# MainBoard.net
KiCad netlist of a schematic drawn in EAGLE
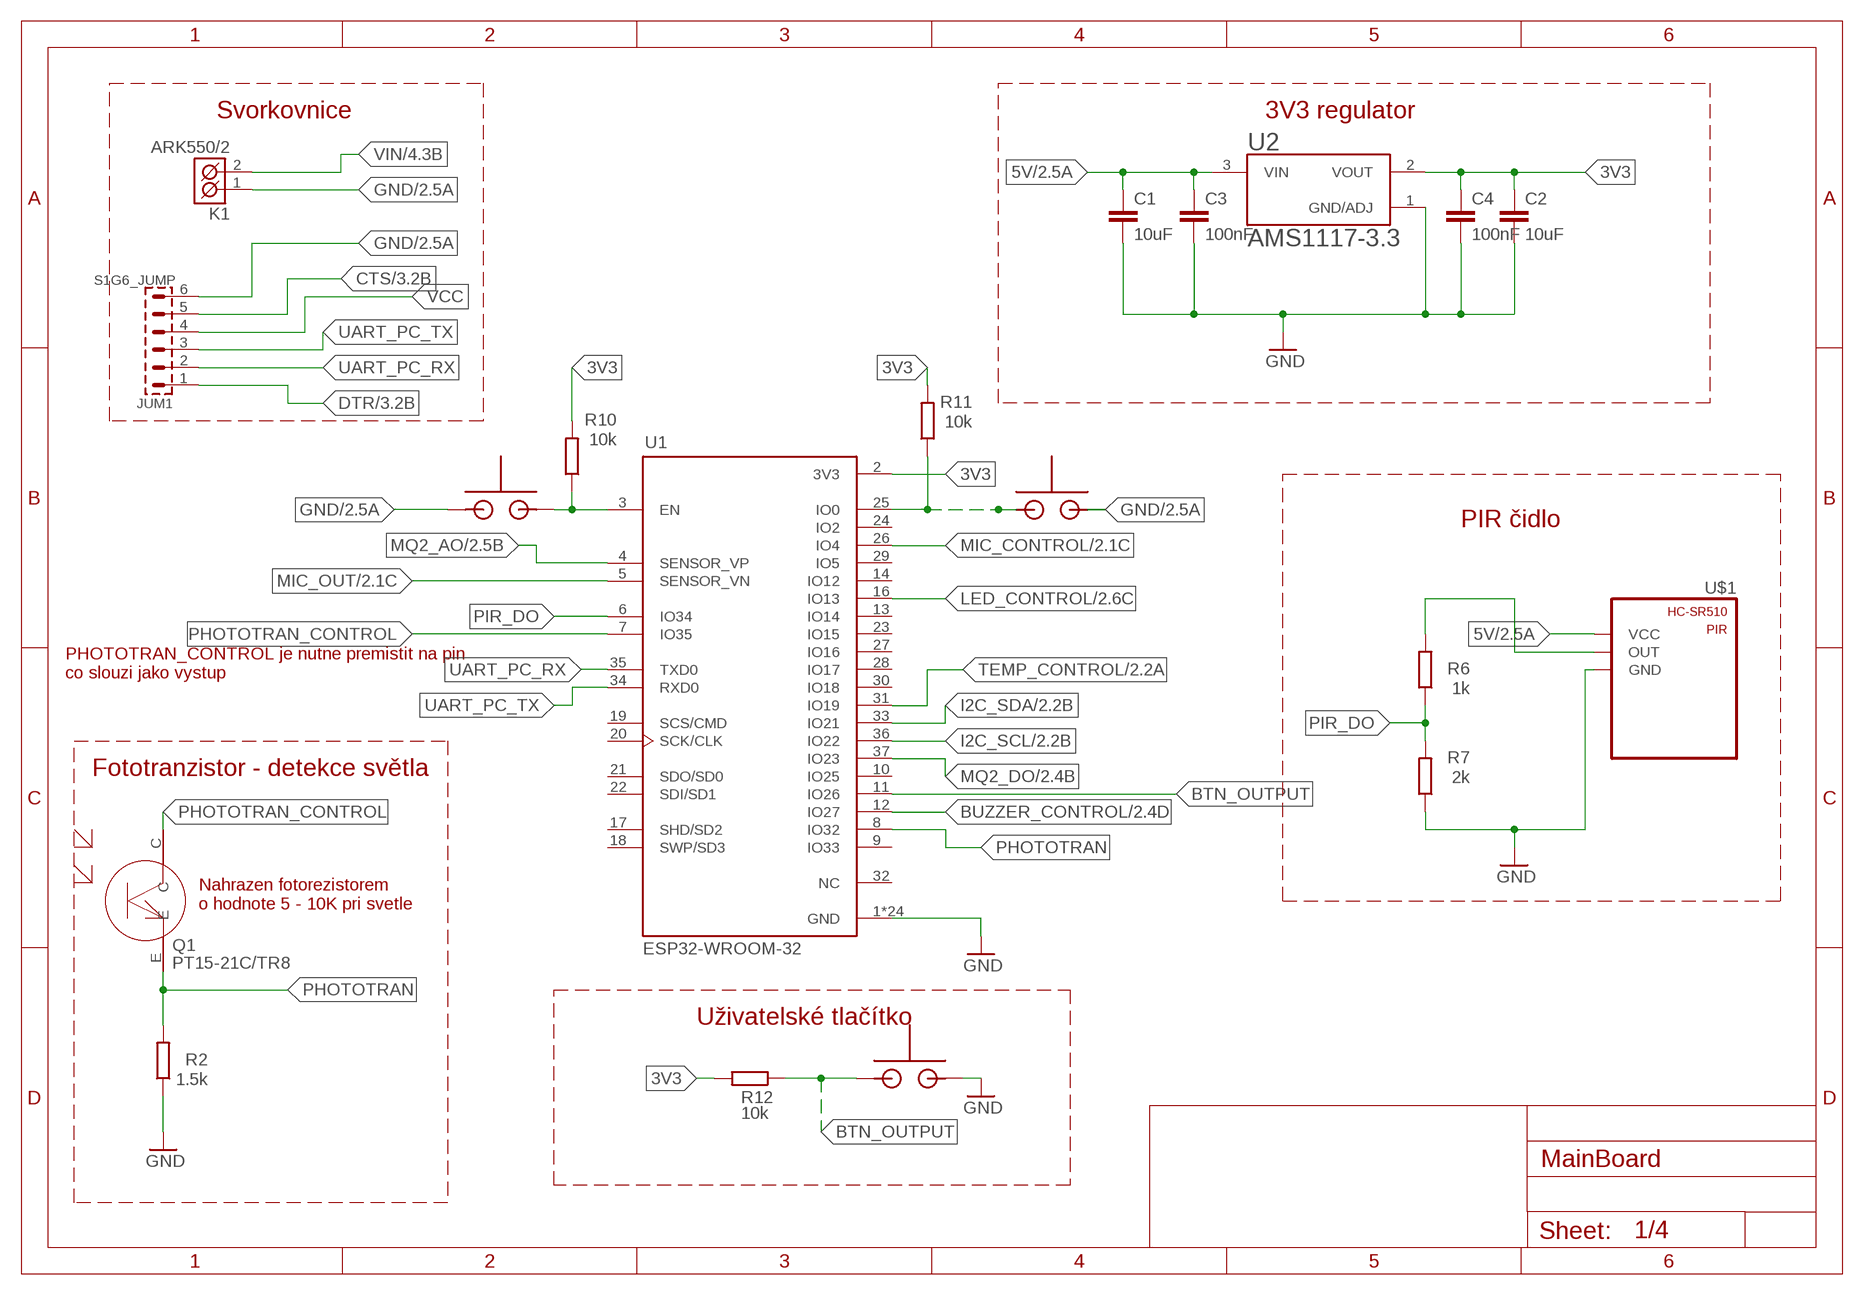
[diagram p0: schematic, sheet 1]
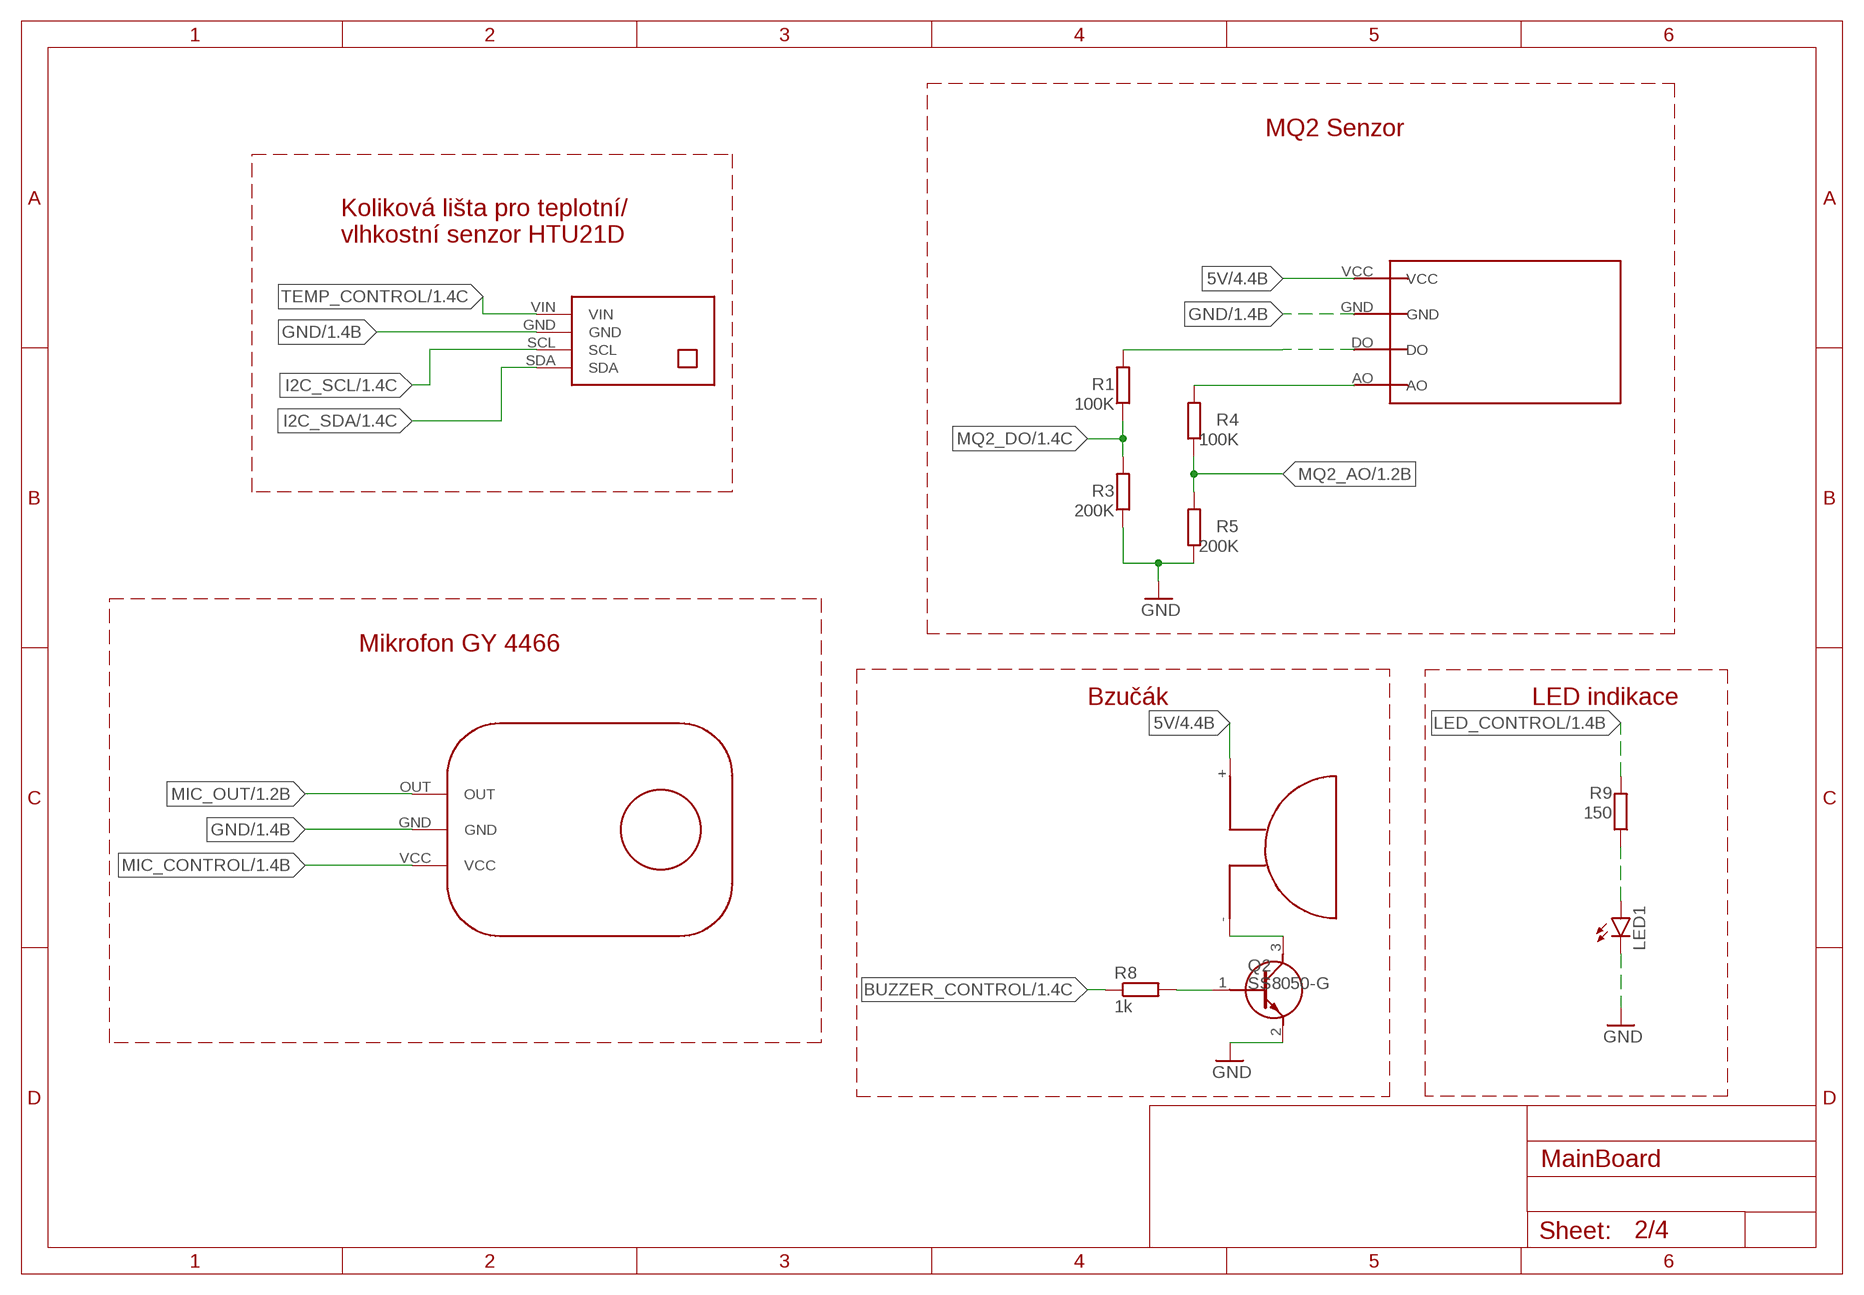
[diagram p1: schematic, sheet 2]
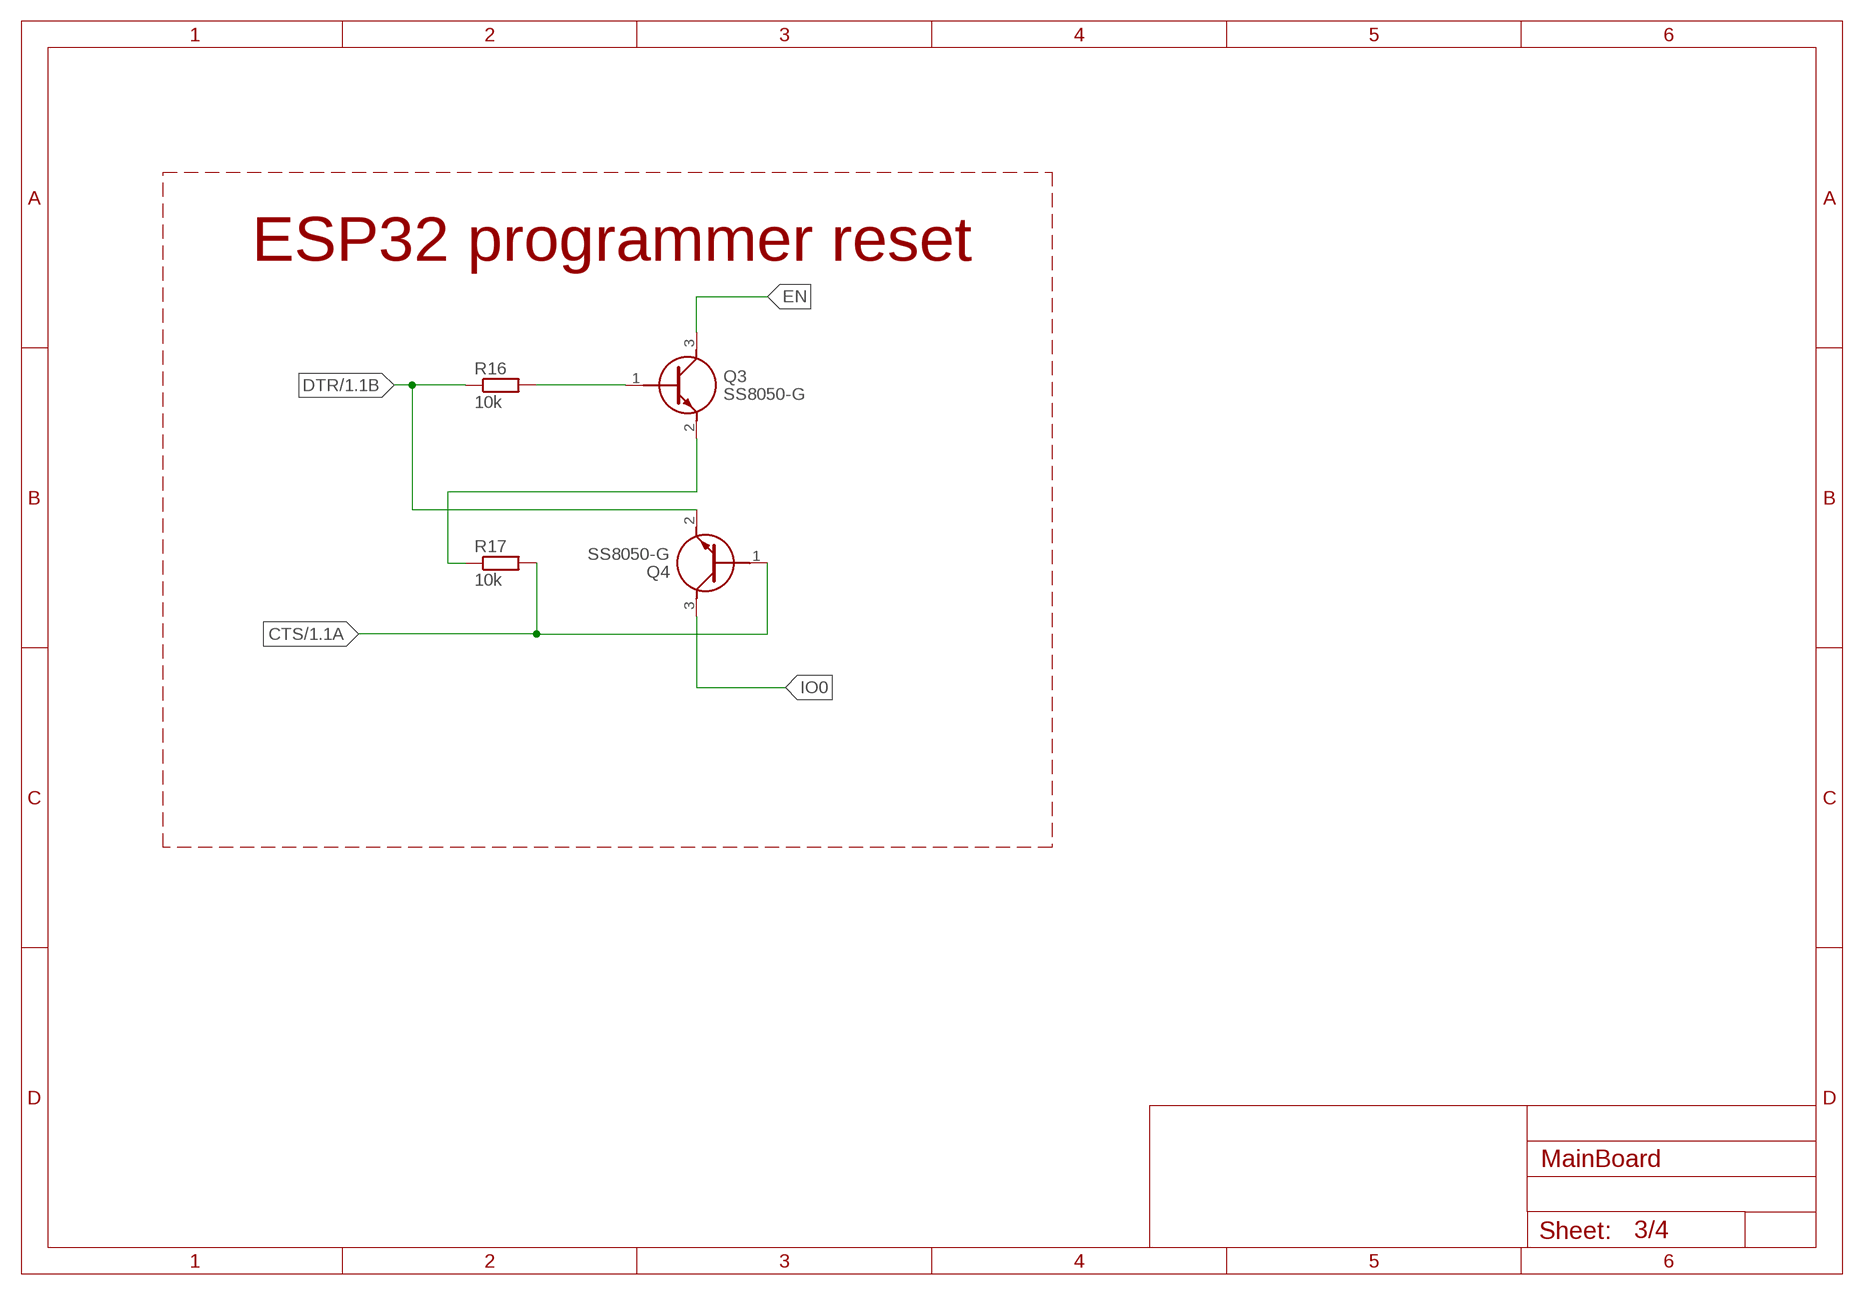
[diagram p2: schematic, sheet 3]
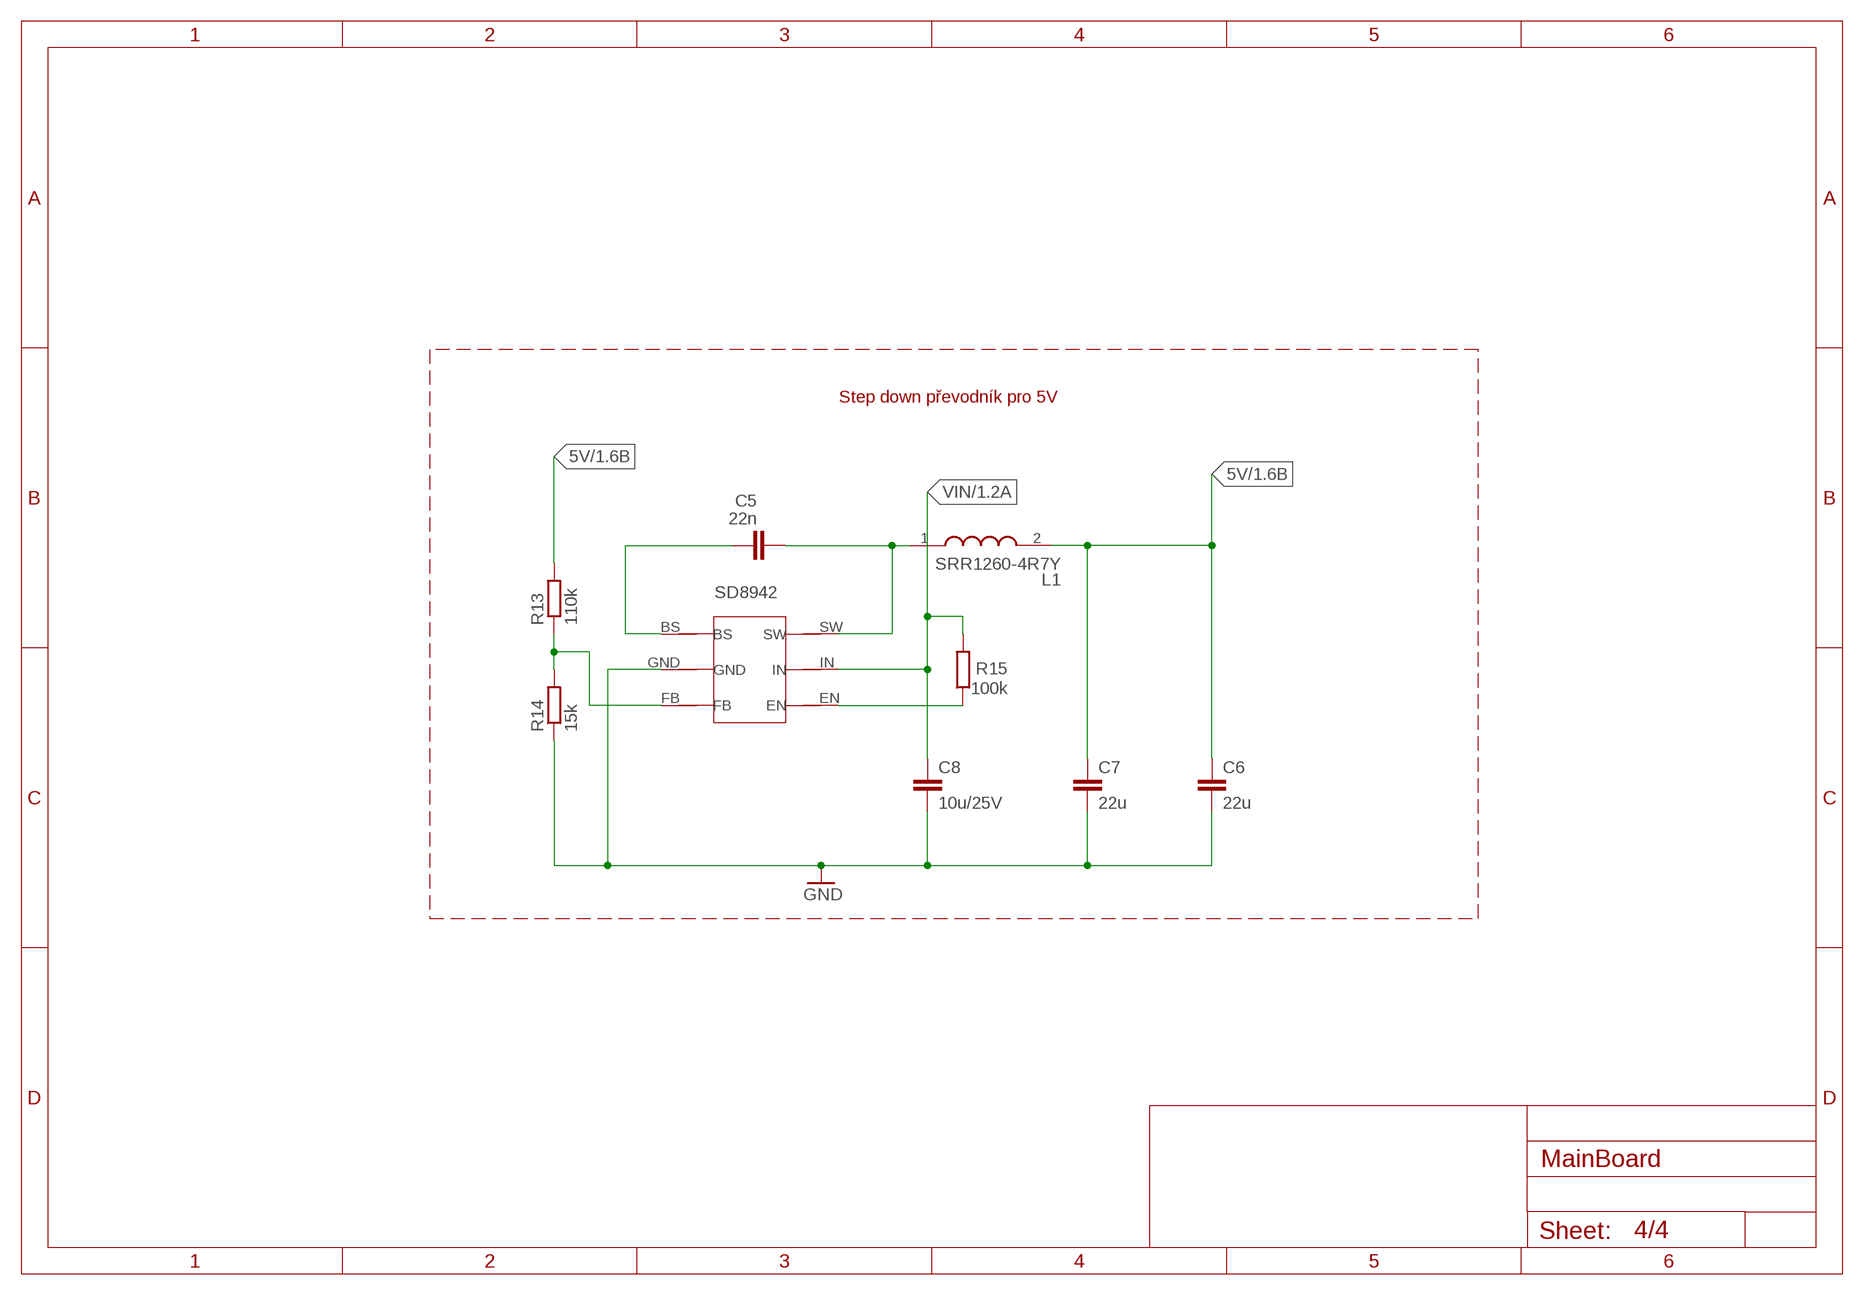
[diagram p3: schematic, sheet 4]

(export (version "E")
  (design (tool "Eeschema 10.0.6"))
  (components
    (comp (ref "C1")
      (value "10uF")
      (footprint "eagle-import:C0805")
      (libsource (lib "eagle-import") (part "C-EUC0805"))
    )
    (comp (ref "C2")
      (value "10uF")
      (footprint "eagle-import:C0805")
      (libsource (lib "eagle-import") (part "C-EUC0805"))
    )
    (comp (ref "C3")
      (value "100nF")
      (footprint "eagle-import:C0805")
      (libsource (lib "eagle-import") (part "C-EUC0805"))
    )
    (comp (ref "C4")
      (value "100nF")
      (footprint "eagle-import:C0805")
      (libsource (lib "eagle-import") (part "C-EUC0805"))
    )
    (comp (ref "JUM1")
      (value "S1G6_JUMP")
      (footprint "eagle-import:S1G6_JUM")
      (libsource (lib "eagle-import") (part "S1G6_JUMP"))
    )
    (comp (ref "K1")
      (value "ARK550/2")
      (footprint "eagle-import:ARK550_2")
      (libsource (lib "eagle-import") (part "ARK550/2"))
    )
    (comp (ref "Q1")
      (value "PT15-21C/TR8")
      (footprint "eagle-import:PT15-21C_TR8")
      (libsource (lib "eagle-import") (part "PT15-21C/TR8"))
    )
    (comp (ref "R2")
      (value "1.5k")
      (footprint "eagle-import:R0805")
      (libsource (lib "eagle-import") (part "R-EU_R0805"))
    )
    (comp (ref "R6")
      (value "1k")
      (footprint "eagle-import:R0805")
      (libsource (lib "eagle-import") (part "R-EU_R0805"))
    )
    (comp (ref "R7")
      (value "2k")
      (footprint "eagle-import:R0805")
      (libsource (lib "eagle-import") (part "R-EU_R0805"))
    )
    (comp (ref "R10")
      (value "10k")
      (footprint "eagle-import:R0805")
      (libsource (lib "eagle-import") (part "R-EU_R0805"))
    )
    (comp (ref "R11")
      (value "10k")
      (footprint "eagle-import:R0805")
      (libsource (lib "eagle-import") (part "R-EU_R0805"))
    )
    (comp (ref "R12")
      (value "10k")
      (footprint "eagle-import:R0805")
      (libsource (lib "eagle-import") (part "R-EU_R0805"))
    )
    (comp (ref "U$1")
      (value "HC-SR501")
      (footprint "eagle-import:HC-SR501")
      (libsource (lib "eagle-import") (part "HC-SR501"))
    )
    (comp (ref "U$6")
      (value "TS6604B")
      (footprint "eagle-import:TS6604B")
      (libsource (lib "eagle-import") (part "TS6604B"))
    )
    (comp (ref "U$7")
      (value "TS6604B")
      (footprint "eagle-import:TS6604B")
      (libsource (lib "eagle-import") (part "TS6604B"))
    )
    (comp (ref "U$8")
      (value "TS6604B")
      (footprint "eagle-import:TS6604B")
      (libsource (lib "eagle-import") (part "TS6604B"))
    )
    (comp (ref "U1")
      (value "ESP32-WROOM-32")
      (footprint "eagle-import:MODULE_ESP32-WROOM-32")
      (fields (field (name "MF") "Espressif Systems"))
      (libsource (lib "eagle-import") (part "ESP32-WROOM-32"))
    )
    (comp (ref "U2")
      (value "AMS1117-3.3")
      (footprint "eagle-import:SOT229P700X180-4N")
      (fields (field (name "MF") "Advanced Monolithic Systems"))
      (libsource (lib "eagle-import") (part "AMS1117-3.3"))
    )
    (comp (ref "LED1")
      (value "LEDCHIP-LED0805")
      (footprint "eagle-import:CHIP-LED0805")
      (libsource (lib "eagle-import") (part "LEDCHIP-LED0805"))
    )
    (comp (ref "Q2")
      (value "SS8050-G")
      (footprint "eagle-import:SOT95P240X115-3N")
      (fields (field (name "MOUSER_PART_NUMBER") "750-SS8050-G"))
      (libsource (lib "eagle-import") (part "SS8050-G"))
    )
    (comp (ref "R1")
      (value "100K")
      (footprint "eagle-import:R0805")
      (libsource (lib "eagle-import") (part "R-EU_R0805"))
    )
    (comp (ref "R3")
      (value "200K")
      (footprint "eagle-import:R0805")
      (libsource (lib "eagle-import") (part "R-EU_R0805"))
    )
    (comp (ref "R4")
      (value "100K")
      (footprint "eagle-import:R0805")
      (libsource (lib "eagle-import") (part "R-EU_R0805"))
    )
    (comp (ref "R5")
      (value "200K")
      (footprint "eagle-import:R0805")
      (libsource (lib "eagle-import") (part "R-EU_R0805"))
    )
    (comp (ref "R8")
      (value "1k")
      (footprint "eagle-import:R0805")
      (libsource (lib "eagle-import") (part "R-EU_R0805"))
    )
    (comp (ref "R9")
      (value "150")
      (footprint "eagle-import:R0805")
      (libsource (lib "eagle-import") (part "R-EU_R0805"))
    )
    (comp (ref "U$2")
      (value "MQ2")
      (footprint "eagle-import:MQ2")
      (libsource (lib "eagle-import") (part "MQ2"))
    )
    (comp (ref "U$3")
      (value "GY4466")
      (footprint "eagle-import:GY4466")
      (libsource (lib "eagle-import") (part "GY4466"))
    )
    (comp (ref "U$4")
      (value "BUZZER")
      (footprint "eagle-import:BUZZER")
      (libsource (lib "eagle-import") (part "BUZZER"))
    )
    (comp (ref "U$5")
      (value "HTU21D")
      (footprint "eagle-import:HTU21D")
      (libsource (lib "eagle-import") (part "HTU21D"))
    )
    (comp (ref "C5")
      (value "22n")
      (footprint "eagle-import:C0805")
      (libsource (lib "eagle-import") (part "C-EUC0805"))
    )
    (comp (ref "C6")
      (value "22u")
      (footprint "eagle-import:C0805")
      (libsource (lib "eagle-import") (part "C-EUC0805"))
    )
    (comp (ref "C7")
      (value "22u")
      (footprint "eagle-import:C0805")
      (libsource (lib "eagle-import") (part "C-EUC0805"))
    )
    (comp (ref "C8")
      (value "10u/25V")
      (footprint "eagle-import:C0805")
      (libsource (lib "eagle-import") (part "C-EUC0805"))
    )
    (comp (ref "L1")
      (value "SRR1260-4R7Y")
      (footprint "eagle-import:SRR12604R7Y")
      (fields (field (name "MOUSER_PART_NUMBER") "652-SRR1260-4R7Y"))
      (libsource (lib "eagle-import") (part "SRR1260-4R7Y"))
    )
    (comp (ref "R13")
      (value "110k")
      (footprint "eagle-import:R0805")
      (libsource (lib "eagle-import") (part "R-EU_R0805"))
    )
    (comp (ref "R14")
      (value "15k")
      (footprint "eagle-import:R0805")
      (libsource (lib "eagle-import") (part "R-EU_R0805"))
    )
    (comp (ref "R15")
      (value "100k")
      (footprint "eagle-import:R0805")
      (libsource (lib "eagle-import") (part "R-EU_R0805"))
    )
    (comp (ref "U$9")
      (value "SD8942")
      (footprint "eagle-import:SD8942")
      (libsource (lib "eagle-import") (part "SD8942"))
    )
    (comp (ref "Q3")
      (value "SS8050-G")
      (footprint "eagle-import:SOT95P240X115-3N")
      (fields (field (name "MOUSER_PART_NUMBER") "750-SS8050-G"))
      (libsource (lib "eagle-import") (part "SS8050-G"))
    )
    (comp (ref "Q4")
      (value "SS8050-G")
      (footprint "eagle-import:SOT95P240X115-3N")
      (fields (field (name "MOUSER_PART_NUMBER") "750-SS8050-G"))
      (libsource (lib "eagle-import") (part "SS8050-G"))
    )
    (comp (ref "R16")
      (value "10k")
      (footprint "eagle-import:R0805")
      (libsource (lib "eagle-import") (part "R-EU_R0805"))
    )
    (comp (ref "R17")
      (value "10k")
      (footprint "eagle-import:R0805")
      (libsource (lib "eagle-import") (part "R-EU_R0805"))
    )
  )
  (nets
    (net (code "1") (name "3V3") (class "Default")
      (node (ref "C2") (pin "1") (pinfunction "1_1") (pintype "passive"))
      (node (ref "C4") (pin "1") (pinfunction "1_1") (pintype "passive"))
      (node (ref "R10") (pin "2") (pinfunction "2_2") (pintype "passive"))
      (node (ref "R11") (pin "2") (pinfunction "2_2") (pintype "passive"))
      (node (ref "R12") (pin "2") (pinfunction "2_2") (pintype "passive"))
      (node (ref "U1") (pin "2") (pinfunction "3V3_2") (pintype "power_in"))
      (node (ref "U2") (pin "2") (pinfunction "VOUT_2") (pintype "output"))
    )
    (net (code "2") (name "5V") (class "Default")
      (node (ref "C1") (pin "1") (pinfunction "1_1") (pintype "passive"))
      (node (ref "C3") (pin "1") (pinfunction "1_1") (pintype "passive"))
      (node (ref "C6") (pin "1") (pinfunction "1_1") (pintype "passive"))
      (node (ref "C7") (pin "1") (pinfunction "1_1") (pintype "passive"))
      (node (ref "L1") (pin "2") (pinfunction "2_2") (pintype "bidirectional"))
      (node (ref "R13") (pin "2") (pinfunction "2_2") (pintype "passive"))
      (node (ref "U$1") (pin "VCC") (pinfunction "VCC_VCC") (pintype "power_in"))
      (node (ref "U$2") (pin "VCC") (pinfunction "VCC_VCC") (pintype "bidirectional"))
      (node (ref "U$4") (pin "+") (pinfunction "+_+") (pintype "bidirectional"))
      (node (ref "U2") (pin "3") (pinfunction "VIN_3") (pintype "input"))
    )
    (net (code "3") (name "BTN_OUTPUT") (class "Default")
      (node (ref "R12") (pin "1") (pinfunction "1_1") (pintype "passive"))
      (node (ref "U$8") (pin "+") (pinfunction "+_+") (pintype "bidirectional"))
      (node (ref "U1") (pin "11") (pinfunction "IO26_11") (pintype "bidirectional"))
    )
    (net (code "4") (name "BUZZER_CONTROL") (class "Default")
      (node (ref "R8") (pin "1") (pinfunction "1_1") (pintype "passive"))
      (node (ref "U1") (pin "12") (pinfunction "IO27_12") (pintype "bidirectional"))
    )
    (net (code "5") (name "CTS") (class "Default")
      (node (ref "JUM1") (pin "5") (pinfunction "5_5") (pintype "passive"))
      (node (ref "Q4") (pin "1") (pinfunction "B_1") (pintype "bidirectional"))
      (node (ref "R17") (pin "2") (pinfunction "2_2") (pintype "passive"))
    )
    (net (code "6") (name "DTR") (class "Default")
      (node (ref "JUM1") (pin "1") (pinfunction "1_1") (pintype "passive"))
      (node (ref "Q4") (pin "2") (pinfunction "E_2") (pintype "bidirectional"))
      (node (ref "R16") (pin "1") (pinfunction "1_1") (pintype "passive"))
    )
    (net (code "7") (name "EN") (class "Default")
      (node (ref "Q3") (pin "3") (pinfunction "C_3") (pintype "bidirectional"))
      (node (ref "R10") (pin "1") (pinfunction "1_1") (pintype "passive"))
      (node (ref "U$6") (pin "+") (pinfunction "+_+") (pintype "bidirectional"))
      (node (ref "U1") (pin "3") (pinfunction "EN_3") (pintype "input"))
    )
    (net (code "8") (name "GND") (class "Default")
      (node (ref "C1") (pin "2") (pinfunction "2_2") (pintype "passive"))
      (node (ref "C2") (pin "2") (pinfunction "2_2") (pintype "passive"))
      (node (ref "C3") (pin "2") (pinfunction "2_2") (pintype "passive"))
      (node (ref "C4") (pin "2") (pinfunction "2_2") (pintype "passive"))
      (node (ref "C6") (pin "2") (pinfunction "2_2") (pintype "passive"))
      (node (ref "C7") (pin "2") (pinfunction "2_2") (pintype "passive"))
      (node (ref "C8") (pin "2") (pinfunction "2_2") (pintype "passive"))
      (node (ref "JUM1") (pin "6") (pinfunction "6_6") (pintype "passive"))
      (node (ref "K1") (pin "1") (pinfunction "K1_1") (pintype "passive"))
      (node (ref "LED1") (pin "C") (pinfunction "C_C") (pintype "passive"))
      (node (ref "Q2") (pin "2") (pinfunction "E_2") (pintype "bidirectional"))
      (node (ref "R14") (pin "1") (pinfunction "1_1") (pintype "passive"))
      (node (ref "R2") (pin "1") (pinfunction "1_1") (pintype "passive"))
      (node (ref "R3") (pin "1") (pinfunction "1_1") (pintype "passive"))
      (node (ref "R5") (pin "1") (pinfunction "1_1") (pintype "passive"))
      (node (ref "R7") (pin "1") (pinfunction "1_1") (pintype "passive"))
      (node (ref "U$1") (pin "GND") (pinfunction "GND_GND") (pintype "power_in"))
      (node (ref "U$2") (pin "GND") (pinfunction "GND_GND") (pintype "bidirectional"))
      (node (ref "U$3") (pin "GND") (pinfunction "GND_GND") (pintype "bidirectional"))
      (node (ref "U$5") (pin "GND") (pinfunction "GND_GND") (pintype "bidirectional"))
      (node (ref "U$6") (pin "-") (pinfunction "-_-") (pintype "bidirectional"))
      (node (ref "U$7") (pin "-") (pinfunction "-_-") (pintype "bidirectional"))
      (node (ref "U$8") (pin "-") (pinfunction "-_-") (pintype "bidirectional"))
      (node (ref "U$9") (pin "GND") (pinfunction "GND_GND") (pintype "bidirectional"))
      (node (ref "U1") (pin "1") (pinfunction "GND_1") (pintype "power_in"))
      (node (ref "U1") (pin "15") (pinfunction "GND_15") (pintype "power_in"))
      (node (ref "U1") (pin "38") (pinfunction "GND_38") (pintype "power_in"))
      (node (ref "U1") (pin "39_1") (pinfunction "GND_39_1") (pintype "power_in"))
      (node (ref "U1") (pin "39_10") (pinfunction "GND_39_10") (pintype "power_in"))
      (node (ref "U1") (pin "39_11") (pinfunction "GND_39_11") (pintype "power_in"))
      (node (ref "U1") (pin "39_12") (pinfunction "GND_39_12") (pintype "power_in"))
      (node (ref "U1") (pin "39_13") (pinfunction "GND_39_13") (pintype "power_in"))
      (node (ref "U1") (pin "39_14") (pinfunction "GND_39_14") (pintype "power_in"))
      (node (ref "U1") (pin "39_15") (pinfunction "GND_39_15") (pintype "power_in"))
      (node (ref "U1") (pin "39_16") (pinfunction "GND_39_16") (pintype "power_in"))
      (node (ref "U1") (pin "39_17") (pinfunction "GND_39_17") (pintype "power_in"))
      (node (ref "U1") (pin "39_18") (pinfunction "GND_39_18") (pintype "power_in"))
      (node (ref "U1") (pin "39_19") (pinfunction "GND_39_19") (pintype "power_in"))
      (node (ref "U1") (pin "39_2") (pinfunction "GND_39_2") (pintype "power_in"))
      (node (ref "U1") (pin "39_20") (pinfunction "GND_39_20") (pintype "power_in"))
      (node (ref "U1") (pin "39_21") (pinfunction "GND_39_21") (pintype "power_in"))
      (node (ref "U1") (pin "39_3") (pinfunction "GND_39_3") (pintype "power_in"))
      (node (ref "U1") (pin "39_4") (pinfunction "GND_39_4") (pintype "power_in"))
      (node (ref "U1") (pin "39_5") (pinfunction "GND_39_5") (pintype "power_in"))
      (node (ref "U1") (pin "39_6") (pinfunction "GND_39_6") (pintype "power_in"))
      (node (ref "U1") (pin "39_7") (pinfunction "GND_39_7") (pintype "power_in"))
      (node (ref "U1") (pin "39_8") (pinfunction "GND_39_8") (pintype "power_in"))
      (node (ref "U1") (pin "39_9") (pinfunction "GND_39_9") (pintype "power_in"))
      (node (ref "U2") (pin "1") (pinfunction "GND/ADJ_1") (pintype "power_in"))
    )
    (net (code "9") (name "I2C_SCL") (class "Default")
      (node (ref "U$5") (pin "SCL") (pinfunction "SCL_SCL") (pintype "bidirectional"))
      (node (ref "U1") (pin "36") (pinfunction "IO22_36") (pintype "bidirectional"))
    )
    (net (code "10") (name "I2C_SDA") (class "Default")
      (node (ref "U$5") (pin "SDA") (pinfunction "SDA_SDA") (pintype "bidirectional"))
      (node (ref "U1") (pin "33") (pinfunction "IO21_33") (pintype "bidirectional"))
    )
    (net (code "11") (name "IO0") (class "Default")
      (node (ref "Q4") (pin "3") (pinfunction "C_3") (pintype "bidirectional"))
      (node (ref "R11") (pin "1") (pinfunction "1_1") (pintype "passive"))
      (node (ref "U$7") (pin "+") (pinfunction "+_+") (pintype "bidirectional"))
      (node (ref "U1") (pin "25") (pinfunction "IO0_25") (pintype "bidirectional"))
    )
    (net (code "12") (name "LED_CONTROL") (class "Default")
      (node (ref "R9") (pin "2") (pinfunction "2_2") (pintype "passive"))
      (node (ref "U1") (pin "16") (pinfunction "IO13_16") (pintype "bidirectional"))
    )
    (net (code "13") (name "MIC_CONTROL") (class "Default")
      (node (ref "U$3") (pin "VCC") (pinfunction "VCC_VCC") (pintype "bidirectional"))
      (node (ref "U1") (pin "26") (pinfunction "IO4_26") (pintype "bidirectional"))
    )
    (net (code "14") (name "MIC_OUT") (class "Default")
      (node (ref "U$3") (pin "OUT") (pinfunction "OUT_OUT") (pintype "bidirectional"))
      (node (ref "U1") (pin "5") (pinfunction "SENSOR_VN_5") (pintype "input"))
    )
    (net (code "15") (name "MQ2_AO") (class "Default")
      (node (ref "R4") (pin "1") (pinfunction "1_1") (pintype "passive"))
      (node (ref "R5") (pin "2") (pinfunction "2_2") (pintype "passive"))
      (node (ref "U1") (pin "4") (pinfunction "SENSOR_VP_4") (pintype "input"))
    )
    (net (code "16") (name "MQ2_DO") (class "Default")
      (node (ref "R1") (pin "1") (pinfunction "1_1") (pintype "passive"))
      (node (ref "R3") (pin "2") (pinfunction "2_2") (pintype "passive"))
      (node (ref "U1") (pin "37") (pinfunction "IO23_37") (pintype "bidirectional"))
    )
    (net (code "17") (name "Net-(C5-Pad1)") (class "Default")
      (node (ref "C5") (pin "1") (pinfunction "1_1") (pintype "passive"))
      (node (ref "U$9") (pin "BS") (pinfunction "BS_BS") (pintype "bidirectional"))
    )
    (net (code "18") (name "Net-(C5-Pad2)") (class "Default")
      (node (ref "C5") (pin "2") (pinfunction "2_2") (pintype "passive"))
      (node (ref "L1") (pin "1") (pinfunction "1_1") (pintype "bidirectional"))
      (node (ref "U$9") (pin "SW") (pinfunction "SW_SW") (pintype "bidirectional"))
    )
    (net (code "19") (name "Net-(LED1-PadA)") (class "Default")
      (node (ref "LED1") (pin "A") (pinfunction "A_A") (pintype "passive"))
      (node (ref "R9") (pin "1") (pinfunction "1_1") (pintype "passive"))
    )
    (net (code "20") (name "Net-(Q2-B)") (class "Default")
      (node (ref "Q2") (pin "1") (pinfunction "B_1") (pintype "bidirectional"))
      (node (ref "R8") (pin "2") (pinfunction "2_2") (pintype "passive"))
    )
    (net (code "21") (name "Net-(Q2-C)") (class "Default")
      (node (ref "Q2") (pin "3") (pinfunction "C_3") (pintype "bidirectional"))
      (node (ref "U$4") (pin "-") (pinfunction "-_-") (pintype "bidirectional"))
    )
    (net (code "22") (name "Net-(Q3-B)") (class "Default")
      (node (ref "Q3") (pin "1") (pinfunction "B_1") (pintype "bidirectional"))
      (node (ref "R16") (pin "2") (pinfunction "2_2") (pintype "passive"))
    )
    (net (code "23") (name "Net-(Q3-E)") (class "Default")
      (node (ref "Q3") (pin "2") (pinfunction "E_2") (pintype "bidirectional"))
      (node (ref "R17") (pin "1") (pinfunction "1_1") (pintype "passive"))
    )
    (net (code "24") (name "Net-(R1-Pad2)") (class "Default")
      (node (ref "R1") (pin "2") (pinfunction "2_2") (pintype "passive"))
      (node (ref "U$2") (pin "DO") (pinfunction "DO_DO") (pintype "bidirectional"))
    )
    (net (code "25") (name "Net-(R4-Pad2)") (class "Default")
      (node (ref "R4") (pin "2") (pinfunction "2_2") (pintype "passive"))
      (node (ref "U$2") (pin "AO") (pinfunction "AO_AO") (pintype "bidirectional"))
    )
    (net (code "26") (name "Net-(R6-Pad2)") (class "Default")
      (node (ref "R6") (pin "2") (pinfunction "2_2") (pintype "passive"))
      (node (ref "U$1") (pin "OUT") (pinfunction "OUT_OUT") (pintype "bidirectional"))
    )
    (net (code "27") (name "Net-(R13-Pad1)") (class "Default")
      (node (ref "R13") (pin "1") (pinfunction "1_1") (pintype "passive"))
      (node (ref "R14") (pin "2") (pinfunction "2_2") (pintype "passive"))
      (node (ref "U$9") (pin "FB") (pinfunction "FB_FB") (pintype "bidirectional"))
    )
    (net (code "28") (name "Net-(R15-Pad1)") (class "Default")
      (node (ref "R15") (pin "1") (pinfunction "1_1") (pintype "passive"))
      (node (ref "U$9") (pin "EN") (pinfunction "EN_EN") (pintype "bidirectional"))
    )
    (net (code "29") (name "PHOTOTRAN") (class "Default")
      (node (ref "Q1") (pin "E") (pinfunction "E_E") (pintype "bidirectional"))
      (node (ref "R2") (pin "2") (pinfunction "2_2") (pintype "passive"))
      (node (ref "U1") (pin "8") (pinfunction "IO32_8") (pintype "bidirectional"))
    )
    (net (code "30") (name "PHOTOTRAN_CONTROL") (class "Default")
      (node (ref "Q1") (pin "C") (pinfunction "C_C") (pintype "bidirectional"))
      (node (ref "U1") (pin "7") (pinfunction "IO35_7") (pintype "input"))
    )
    (net (code "31") (name "PIR_DO") (class "Default")
      (node (ref "R6") (pin "1") (pinfunction "1_1") (pintype "passive"))
      (node (ref "R7") (pin "2") (pinfunction "2_2") (pintype "passive"))
      (node (ref "U1") (pin "6") (pinfunction "IO34_6") (pintype "input"))
    )
    (net (code "32") (name "TEMP_CONTROL") (class "Default")
      (node (ref "U$5") (pin "VIN") (pinfunction "VIN_VIN") (pintype "bidirectional"))
      (node (ref "U1") (pin "31") (pinfunction "IO19_31") (pintype "bidirectional"))
    )
    (net (code "33") (name "UART_PC_RX") (class "Default")
      (node (ref "JUM1") (pin "2") (pinfunction "2_2") (pintype "passive"))
      (node (ref "U1") (pin "35") (pinfunction "TXD0_35") (pintype "bidirectional"))
    )
    (net (code "34") (name "UART_PC_TX") (class "Default")
      (node (ref "JUM1") (pin "3") (pinfunction "3_3") (pintype "passive"))
      (node (ref "U1") (pin "34") (pinfunction "RXD0_34") (pintype "bidirectional"))
    )
    (net (code "35") (name "VCC") (class "Default")
      (node (ref "JUM1") (pin "4") (pinfunction "4_4") (pintype "passive"))
    )
    (net (code "36") (name "VIN") (class "Default")
      (node (ref "C8") (pin "1") (pinfunction "1_1") (pintype "passive"))
      (node (ref "K1") (pin "2") (pinfunction "K2_2") (pintype "passive"))
      (node (ref "R15") (pin "2") (pinfunction "2_2") (pintype "passive"))
      (node (ref "U$9") (pin "IN") (pinfunction "IN_IN") (pintype "bidirectional"))
    )
    (net (code "37") (name "unconnected-(U1-IO2-Pad24)") (class "Default")
      (node (ref "U1") (pin "24") (pinfunction "IO2_24") (pintype "bidirectional"))
    )
    (net (code "38") (name "unconnected-(U1-IO5-Pad29)") (class "Default")
      (node (ref "U1") (pin "29") (pinfunction "IO5_29") (pintype "bidirectional"))
    )
    (net (code "39") (name "unconnected-(U1-IO12-Pad14)") (class "Default")
      (node (ref "U1") (pin "14") (pinfunction "IO12_14") (pintype "bidirectional"))
    )
    (net (code "40") (name "unconnected-(U1-IO14-Pad13)") (class "Default")
      (node (ref "U1") (pin "13") (pinfunction "IO14_13") (pintype "bidirectional"))
    )
    (net (code "41") (name "unconnected-(U1-IO15-Pad23)") (class "Default")
      (node (ref "U1") (pin "23") (pinfunction "IO15_23") (pintype "bidirectional"))
    )
    (net (code "42") (name "unconnected-(U1-IO16-Pad27)") (class "Default")
      (node (ref "U1") (pin "27") (pinfunction "IO16_27") (pintype "bidirectional"))
    )
    (net (code "43") (name "unconnected-(U1-IO17-Pad28)") (class "Default")
      (node (ref "U1") (pin "28") (pinfunction "IO17_28") (pintype "bidirectional"))
    )
    (net (code "44") (name "unconnected-(U1-IO18-Pad30)") (class "Default")
      (node (ref "U1") (pin "30") (pinfunction "IO18_30") (pintype "bidirectional"))
    )
    (net (code "45") (name "unconnected-(U1-IO25-Pad10)") (class "Default")
      (node (ref "U1") (pin "10") (pinfunction "IO25_10") (pintype "bidirectional"))
    )
    (net (code "46") (name "unconnected-(U1-IO33-Pad9)") (class "Default")
      (node (ref "U1") (pin "9") (pinfunction "IO33_9") (pintype "bidirectional"))
    )
    (net (code "47") (name "unconnected-(U1-NC-Pad32)") (class "Default")
      (node (ref "U1") (pin "32") (pinfunction "NC_32") (pintype "no_connect"))
    )
    (net (code "48") (name "unconnected-(U1-SCK{slash}CLK-Pad20)") (class "Default")
      (node (ref "U1") (pin "20") (pinfunction "SCK/CLK_20") (pintype "bidirectional"))
    )
    (net (code "49") (name "unconnected-(U1-SCS{slash}CMD-Pad19)") (class "Default")
      (node (ref "U1") (pin "19") (pinfunction "SCS/CMD_19") (pintype "bidirectional"))
    )
    (net (code "50") (name "unconnected-(U1-SDI{slash}SD1-Pad22)") (class "Default")
      (node (ref "U1") (pin "22") (pinfunction "SDI/SD1_22") (pintype "bidirectional"))
    )
    (net (code "51") (name "unconnected-(U1-SDO{slash}SD0-Pad21)") (class "Default")
      (node (ref "U1") (pin "21") (pinfunction "SDO/SD0_21") (pintype "bidirectional"))
    )
    (net (code "52") (name "unconnected-(U1-SHD{slash}SD2-Pad17)") (class "Default")
      (node (ref "U1") (pin "17") (pinfunction "SHD/SD2_17") (pintype "bidirectional"))
    )
    (net (code "53") (name "unconnected-(U1-SWP{slash}SD3-Pad18)") (class "Default")
      (node (ref "U1") (pin "18") (pinfunction "SWP/SD3_18") (pintype "bidirectional"))
    )
  )
)
